# supply.net
KiCad netlist of a schematic drawn in EAGLE
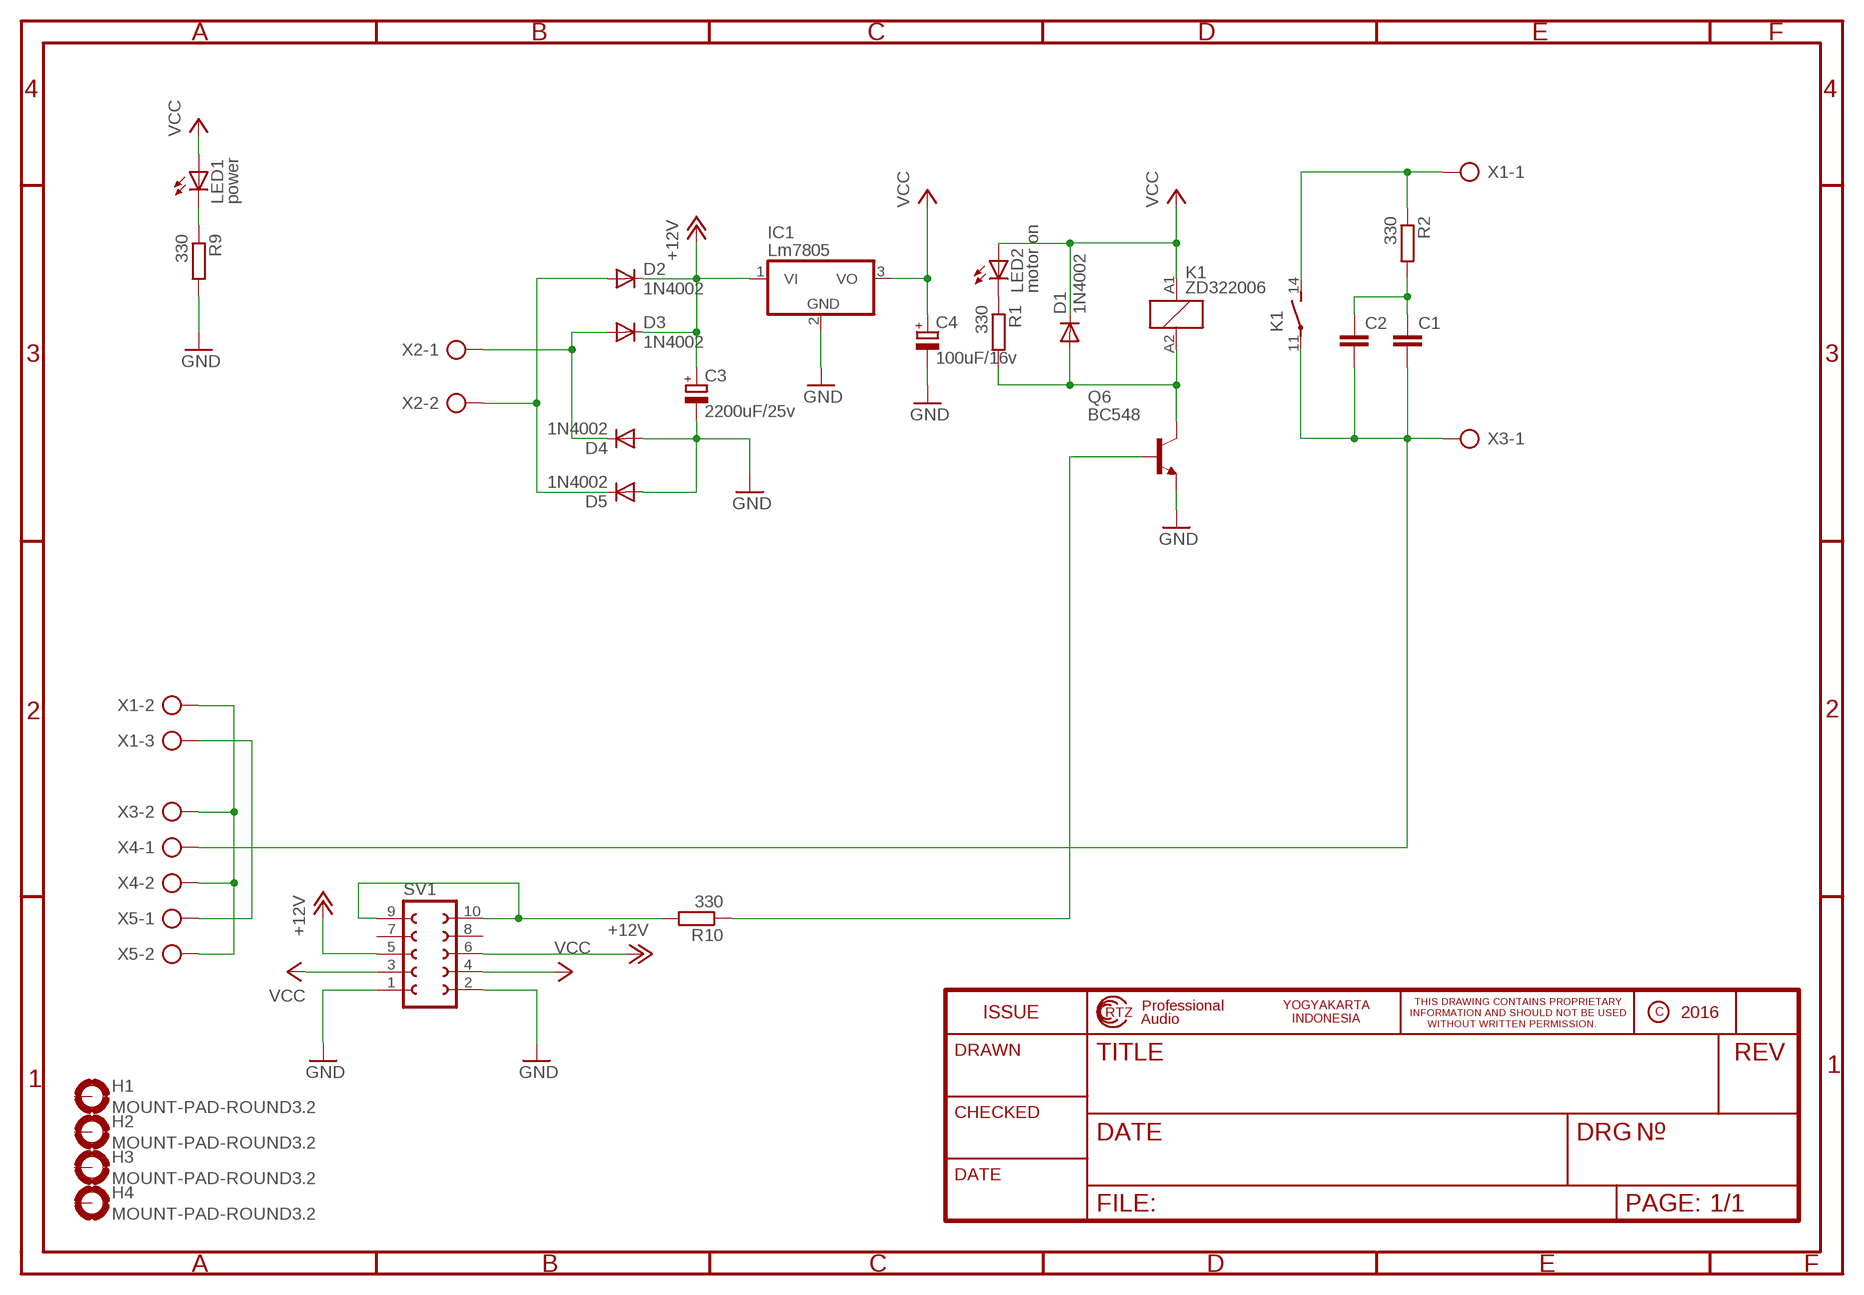
[diagram p0: schematic, sheet 1]

(export (version "E")
  (design (tool "Eeschema 10.0.6"))
  (components
    (comp (ref "C1")
      (value "C-EU150-084X183")
      (footprint "eagle-import:C150-084X183")
      (libsource (lib "eagle-import") (part "C-EU150-084X183"))
    )
    (comp (ref "C2")
      (value "C-EU102-043X133")
      (footprint "eagle-import:C102-043X133")
      (libsource (lib "eagle-import") (part "C-EU102-043X133"))
    )
    (comp (ref "C3")
      (value "2200uF/25v")
      (footprint "eagle-import:E5-8,5")
      (libsource (lib "eagle-import") (part "CPOL-EUE5-8.5"))
    )
    (comp (ref "C4")
      (value "100uF/16v")
      (footprint "eagle-import:B45181B")
      (libsource (lib "eagle-import") (part "CPOL-EUB45181B"))
    )
    (comp (ref "D1")
      (value "1N4002")
      (footprint "eagle-import:DO35-10")
      (libsource (lib "eagle-import") (part "1N4446"))
    )
    (comp (ref "D2")
      (value "1N4002")
      (footprint "eagle-import:DO35-10")
      (libsource (lib "eagle-import") (part "1N4446"))
    )
    (comp (ref "D3")
      (value "1N4002")
      (footprint "eagle-import:DO35-10")
      (libsource (lib "eagle-import") (part "1N4446"))
    )
    (comp (ref "D4")
      (value "1N4002")
      (footprint "eagle-import:DO35-10")
      (libsource (lib "eagle-import") (part "1N4446"))
    )
    (comp (ref "D5")
      (value "1N4002")
      (footprint "eagle-import:DO35-10")
      (libsource (lib "eagle-import") (part "1N4446"))
    )
    (comp (ref "H1")
      (value "MOUNT-PAD-ROUND3.2")
      (footprint "eagle-import:3,2-PAD")
      (libsource (lib "eagle-import") (part "MOUNT-PAD-ROUND3.2"))
    )
    (comp (ref "H2")
      (value "MOUNT-PAD-ROUND3.2")
      (footprint "eagle-import:3,2-PAD")
      (libsource (lib "eagle-import") (part "MOUNT-PAD-ROUND3.2"))
    )
    (comp (ref "H3")
      (value "MOUNT-PAD-ROUND3.2")
      (footprint "eagle-import:3,2-PAD")
      (libsource (lib "eagle-import") (part "MOUNT-PAD-ROUND3.2"))
    )
    (comp (ref "H4")
      (value "MOUNT-PAD-ROUND3.2")
      (footprint "eagle-import:3,2-PAD")
      (libsource (lib "eagle-import") (part "MOUNT-PAD-ROUND3.2"))
    )
    (comp (ref "IC1")
      (value "Lm7805")
      (footprint "eagle-import:TO220V")
      (libsource (lib "eagle-import") (part "78TV15"))
    )
    (comp (ref "K1")
      (value "ZD322006")
      (footprint "eagle-import:ZD2")
      (libsource (lib "eagle-import") (part "ZD?232006"))
    )
    (comp (ref "LED1")
      (value "power")
      (footprint "eagle-import:LED5MM")
      (libsource (lib "eagle-import") (part "LED5MM"))
    )
    (comp (ref "LED2")
      (value "motor on")
      (footprint "eagle-import:LED5MM")
      (libsource (lib "eagle-import") (part "LED5MM"))
    )
    (comp (ref "Q6")
      (value "BC548")
      (footprint "eagle-import:TO92-EBC")
      (libsource (lib "eagle-import") (part "BC548"))
    )
    (comp (ref "R1")
      (value "330")
      (footprint "eagle-import:0207_7")
      (libsource (lib "eagle-import") (part "R-EU_0207/7"))
    )
    (comp (ref "R2")
      (value "330")
      (footprint "eagle-import:0207_7")
      (libsource (lib "eagle-import") (part "R-EU_0207/7"))
    )
    (comp (ref "R9")
      (value "330")
      (footprint "eagle-import:0207_7")
      (libsource (lib "eagle-import") (part "R-EU_0207/7"))
    )
    (comp (ref "R10")
      (value "330")
      (footprint "eagle-import:0207_7")
      (libsource (lib "eagle-import") (part "R-EU_0207/7"))
    )
    (comp (ref "SV1")
      (value "FE05-2")
      (footprint "eagle-import:FE05-2")
      (libsource (lib "eagle-import") (part "FE05-2"))
    )
    (comp (ref "X1")
      (value "AK500/3")
      (footprint "eagle-import:AK500_3")
      (libsource (lib "eagle-import") (part "AK500/3"))
    )
    (comp (ref "X2")
      (value "AK500/2")
      (footprint "eagle-import:AK500_2")
      (libsource (lib "eagle-import") (part "AK500/2"))
    )
    (comp (ref "X3")
      (value "AK500/2")
      (footprint "eagle-import:AK500_2")
      (libsource (lib "eagle-import") (part "AK500/2"))
    )
    (comp (ref "X4")
      (value "AK500/2")
      (footprint "eagle-import:AK500_2")
      (libsource (lib "eagle-import") (part "AK500/2"))
    )
    (comp (ref "X5")
      (value "AK500/2")
      (footprint "eagle-import:AK500_2")
      (libsource (lib "eagle-import") (part "AK500/2"))
    )
  )
  (nets
    (net (code "1") (name "+12V") (class "Default")
      (node (ref "C3") (pin "+") (pinfunction "+_+") (pintype "passive"))
      (node (ref "D2") (pin "C") (pinfunction "C_C") (pintype "passive"))
      (node (ref "D3") (pin "C") (pinfunction "C_C") (pintype "passive"))
      (node (ref "IC1") (pin "1") (pinfunction "VI_1") (pintype "input"))
      (node (ref "SV1") (pin "5") (pinfunction "5_5") (pintype "passive"))
      (node (ref "SV1") (pin "6") (pinfunction "6_6") (pintype "passive"))
    )
    (net (code "2") (name "GND") (class "Default")
      (node (ref "C3") (pin "-") (pinfunction "-_-") (pintype "passive"))
      (node (ref "C4") (pin "-") (pinfunction "-_-") (pintype "passive"))
      (node (ref "D4") (pin "A") (pinfunction "A_A") (pintype "passive"))
      (node (ref "D5") (pin "A") (pinfunction "A_A") (pintype "passive"))
      (node (ref "IC1") (pin "2") (pinfunction "GND_2") (pintype "passive"))
      (node (ref "Q6") (pin "E") (pinfunction "E_E") (pintype "passive"))
      (node (ref "R9") (pin "2") (pinfunction "2_2") (pintype "passive"))
      (node (ref "SV1") (pin "1") (pinfunction "1_1") (pintype "passive"))
      (node (ref "SV1") (pin "2") (pinfunction "2_2") (pintype "passive"))
    )
    (net (code "3") (name "Net-(C1-Pad1)") (class "Default")
      (node (ref "C1") (pin "1") (pinfunction "1_1") (pintype "passive"))
      (node (ref "C2") (pin "1") (pinfunction "1_1") (pintype "passive"))
      (node (ref "R2") (pin "2") (pinfunction "2_2") (pintype "passive"))
    )
    (net (code "4") (name "Net-(K1A-2)") (class "Default")
      (node (ref "D1") (pin "A") (pinfunction "A_A") (pintype "passive"))
      (node (ref "K1") (pin "A2") (pinfunction "2_A2") (pintype "passive"))
      (node (ref "Q6") (pin "C") (pinfunction "C_C") (pintype "passive"))
      (node (ref "R1") (pin "2") (pinfunction "2_2") (pintype "passive"))
    )
    (net (code "5") (name "Net-(K1B-P)") (class "Default")
      (node (ref "C1") (pin "2") (pinfunction "2_2") (pintype "passive"))
      (node (ref "C2") (pin "2") (pinfunction "2_2") (pintype "passive"))
      (node (ref "K1") (pin "11") (pinfunction "P_11") (pintype "passive"))
      (node (ref "X3") (pin "1") (pinfunction "KL_1") (pintype "passive"))
      (node (ref "X4") (pin "1") (pinfunction "KL_1") (pintype "passive"))
    )
    (net (code "6") (name "Net-(K1B-S)") (class "Default")
      (node (ref "K1") (pin "14") (pinfunction "S_14") (pintype "passive"))
      (node (ref "R2") (pin "1") (pinfunction "1_1") (pintype "passive"))
      (node (ref "X1") (pin "1") (pinfunction "KL_1") (pintype "passive"))
    )
    (net (code "7") (name "Net-(LED1-C)") (class "Default")
      (node (ref "LED1") (pin "K") (pinfunction "C_K") (pintype "passive"))
      (node (ref "R9") (pin "1") (pinfunction "1_1") (pintype "passive"))
    )
    (net (code "8") (name "Net-(LED2-C)") (class "Default")
      (node (ref "LED2") (pin "K") (pinfunction "C_K") (pintype "passive"))
      (node (ref "R1") (pin "1") (pinfunction "1_1") (pintype "passive"))
    )
    (net (code "9") (name "Net-(Q6-PadB)") (class "Default")
      (node (ref "Q6") (pin "B") (pinfunction "B_B") (pintype "passive"))
      (node (ref "R10") (pin "1") (pinfunction "1_1") (pintype "passive"))
    )
    (net (code "10") (name "Net-(R10-Pad2)") (class "Default")
      (node (ref "R10") (pin "2") (pinfunction "2_2") (pintype "passive"))
      (node (ref "SV1") (pin "10") (pinfunction "10_10") (pintype "passive"))
      (node (ref "SV1") (pin "9") (pinfunction "9_9") (pintype "passive"))
    )
    (net (code "11") (name "Net-(X1B-KL)") (class "Default")
      (node (ref "X1") (pin "2") (pinfunction "KL_2") (pintype "passive"))
      (node (ref "X3") (pin "2") (pinfunction "KL_2") (pintype "passive"))
      (node (ref "X4") (pin "2") (pinfunction "KL_2") (pintype "passive"))
      (node (ref "X5") (pin "2") (pinfunction "KL_2") (pintype "passive"))
    )
    (net (code "12") (name "Net-(X1C-KL)") (class "Default")
      (node (ref "X1") (pin "3") (pinfunction "KL_3") (pintype "passive"))
      (node (ref "X5") (pin "1") (pinfunction "KL_1") (pintype "passive"))
    )
    (net (code "13") (name "Net-(X2A-KL)") (class "Default")
      (node (ref "D3") (pin "A") (pinfunction "A_A") (pintype "passive"))
      (node (ref "D4") (pin "C") (pinfunction "C_C") (pintype "passive"))
      (node (ref "X2") (pin "1") (pinfunction "KL_1") (pintype "passive"))
    )
    (net (code "14") (name "Net-(X2B-KL)") (class "Default")
      (node (ref "D2") (pin "A") (pinfunction "A_A") (pintype "passive"))
      (node (ref "D5") (pin "C") (pinfunction "C_C") (pintype "passive"))
      (node (ref "X2") (pin "2") (pinfunction "KL_2") (pintype "passive"))
    )
    (net (code "15") (name "VCC") (class "Default")
      (node (ref "C4") (pin "+") (pinfunction "+_+") (pintype "passive"))
      (node (ref "D1") (pin "C") (pinfunction "C_C") (pintype "passive"))
      (node (ref "IC1") (pin "3") (pinfunction "VO_3") (pintype "passive"))
      (node (ref "K1") (pin "A1") (pinfunction "1_A1") (pintype "passive"))
      (node (ref "LED1") (pin "A") (pinfunction "A_A") (pintype "passive"))
      (node (ref "LED2") (pin "A") (pinfunction "A_A") (pintype "passive"))
      (node (ref "SV1") (pin "3") (pinfunction "3_3") (pintype "passive"))
      (node (ref "SV1") (pin "4") (pinfunction "4_4") (pintype "passive"))
    )
    (net (code "16") (name "unconnected-(H1-MOUNT-PadB3,2)") (class "Default")
      (node (ref "H1") (pin "B3,2") (pinfunction "MOUNT_B3,2") (pintype "passive"))
    )
    (net (code "17") (name "unconnected-(H2-MOUNT-PadB3,2)") (class "Default")
      (node (ref "H2") (pin "B3,2") (pinfunction "MOUNT_B3,2") (pintype "passive"))
    )
    (net (code "18") (name "unconnected-(H3-MOUNT-PadB3,2)") (class "Default")
      (node (ref "H3") (pin "B3,2") (pinfunction "MOUNT_B3,2") (pintype "passive"))
    )
    (net (code "19") (name "unconnected-(H4-MOUNT-PadB3,2)") (class "Default")
      (node (ref "H4") (pin "B3,2") (pinfunction "MOUNT_B3,2") (pintype "passive"))
    )
    (net (code "20") (name "unconnected-(SV1-Pad7)") (class "Default")
      (node (ref "SV1") (pin "7") (pinfunction "7_7") (pintype "passive"))
    )
    (net (code "21") (name "unconnected-(SV1-Pad8)") (class "Default")
      (node (ref "SV1") (pin "8") (pinfunction "8_8") (pintype "passive"))
    )
  )
)
